# mcu.net
KiCad netlist of a schematic drawn in Altium Designer
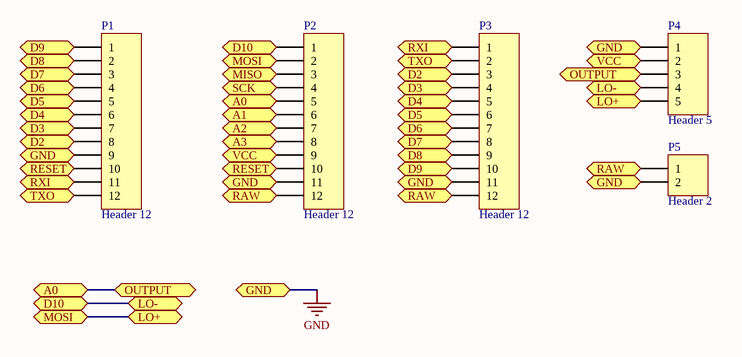
[diagram p0: mcu.SchDoc]

(export (version "E")
  (design (tool "Eeschema 10.0.6"))
  (components
    (comp (ref "P1")
      (value "Header 12")
      (footprint "HDR1X12")
      (description "Header, 12-Pin")
      (fields (field (name "PUBLISHER") "Altium Limited"))
      (libsource (lib "Miscellaneous Connectors") (part "Header 12"))
    )
    (comp (ref "P2")
      (value "Header 12")
      (footprint "HDR1X12")
      (description "Header, 12-Pin")
      (fields (field (name "PUBLISHER") "Altium Limited"))
      (libsource (lib "Miscellaneous Connectors") (part "Header 12"))
    )
    (comp (ref "P3")
      (value "Header 12")
      (footprint "HDR1X12")
      (description "Header, 12-Pin")
      (fields (field (name "PUBLISHER") "Altium Limited"))
      (libsource (lib "Miscellaneous Connectors") (part "Header 12"))
    )
    (comp (ref "P4")
      (value "Header 5")
      (footprint "HDR1X5")
      (description "Header, 5-Pin")
      (fields (field (name "PUBLISHER") "Altium Limited"))
      (libsource (lib "Miscellaneous Connectors") (part "Header 5"))
    )
    (comp (ref "P5")
      (value "Header 2")
      (footprint "HDR1X2")
      (description "Header, 2-Pin")
      (fields (field (name "PUBLISHER") "Altium Limited"))
      (libsource (lib "Miscellaneous Connectors") (part "Header 2"))
    )
  )
  (nets
    (net (code "1") (name "/A0") (class "Default")
      (node (ref "P2") (pin "5") (pinfunction "5_5") (pintype "passive"))
      (node (ref "P4") (pin "3") (pinfunction "3_3") (pintype "passive"))
    )
    (net (code "2") (name "/A1") (class "Default")
      (node (ref "P2") (pin "6") (pinfunction "6_6") (pintype "passive"))
    )
    (net (code "3") (name "/A2") (class "Default")
      (node (ref "P2") (pin "7") (pinfunction "7_7") (pintype "passive"))
    )
    (net (code "4") (name "/A3") (class "Default")
      (node (ref "P2") (pin "8") (pinfunction "8_8") (pintype "passive"))
    )
    (net (code "5") (name "/D2") (class "Default")
      (node (ref "P1") (pin "8") (pinfunction "8_8") (pintype "passive"))
      (node (ref "P3") (pin "3") (pinfunction "3_3") (pintype "passive"))
    )
    (net (code "6") (name "/D3") (class "Default")
      (node (ref "P1") (pin "7") (pinfunction "7_7") (pintype "passive"))
      (node (ref "P3") (pin "4") (pinfunction "4_4") (pintype "passive"))
    )
    (net (code "7") (name "/D4") (class "Default")
      (node (ref "P1") (pin "6") (pinfunction "6_6") (pintype "passive"))
      (node (ref "P3") (pin "5") (pinfunction "5_5") (pintype "passive"))
    )
    (net (code "8") (name "/D5") (class "Default")
      (node (ref "P1") (pin "5") (pinfunction "5_5") (pintype "passive"))
      (node (ref "P3") (pin "6") (pinfunction "6_6") (pintype "passive"))
    )
    (net (code "9") (name "/D6") (class "Default")
      (node (ref "P1") (pin "4") (pinfunction "4_4") (pintype "passive"))
      (node (ref "P3") (pin "7") (pinfunction "7_7") (pintype "passive"))
    )
    (net (code "10") (name "/D7") (class "Default")
      (node (ref "P1") (pin "3") (pinfunction "3_3") (pintype "passive"))
      (node (ref "P3") (pin "8") (pinfunction "8_8") (pintype "passive"))
    )
    (net (code "11") (name "/D8") (class "Default")
      (node (ref "P1") (pin "2") (pinfunction "2_2") (pintype "passive"))
      (node (ref "P3") (pin "9") (pinfunction "9_9") (pintype "passive"))
    )
    (net (code "12") (name "/D9") (class "Default")
      (node (ref "P1") (pin "1") (pinfunction "1_1") (pintype "passive"))
      (node (ref "P3") (pin "10") (pinfunction "10_10") (pintype "passive"))
    )
    (net (code "13") (name "/D10") (class "Default")
      (node (ref "P2") (pin "1") (pinfunction "1_1") (pintype "passive"))
      (node (ref "P4") (pin "4") (pinfunction "4_4") (pintype "passive"))
    )
    (net (code "14") (name "/LO+") (class "Default")
      (node (ref "P2") (pin "2") (pinfunction "2_2") (pintype "passive"))
      (node (ref "P4") (pin "5") (pinfunction "5_5") (pintype "passive"))
    )
    (net (code "15") (name "/MISO") (class "Default")
      (node (ref "P2") (pin "3") (pinfunction "3_3") (pintype "passive"))
    )
    (net (code "16") (name "/RAW") (class "Default")
      (node (ref "P2") (pin "12") (pinfunction "12_12") (pintype "passive"))
      (node (ref "P3") (pin "12") (pinfunction "12_12") (pintype "passive"))
      (node (ref "P5") (pin "1") (pinfunction "1_1") (pintype "passive"))
    )
    (net (code "17") (name "/RESET") (class "Default")
      (node (ref "P1") (pin "10") (pinfunction "10_10") (pintype "passive"))
      (node (ref "P2") (pin "10") (pinfunction "10_10") (pintype "passive"))
    )
    (net (code "18") (name "/RXI") (class "Default")
      (node (ref "P1") (pin "11") (pinfunction "11_11") (pintype "passive"))
      (node (ref "P3") (pin "1") (pinfunction "1_1") (pintype "passive"))
    )
    (net (code "19") (name "/SCK") (class "Default")
      (node (ref "P2") (pin "4") (pinfunction "4_4") (pintype "passive"))
    )
    (net (code "20") (name "/TXO") (class "Default")
      (node (ref "P1") (pin "12") (pinfunction "12_12") (pintype "passive"))
      (node (ref "P3") (pin "2") (pinfunction "2_2") (pintype "passive"))
    )
    (net (code "21") (name "/VCC") (class "Default")
      (node (ref "P2") (pin "9") (pinfunction "9_9") (pintype "passive"))
      (node (ref "P4") (pin "2") (pinfunction "2_2") (pintype "passive"))
    )
    (net (code "22") (name "GND") (class "Default")
      (node (ref "P1") (pin "9") (pinfunction "9_9") (pintype "passive"))
      (node (ref "P2") (pin "11") (pinfunction "11_11") (pintype "passive"))
      (node (ref "P3") (pin "11") (pinfunction "11_11") (pintype "passive"))
      (node (ref "P4") (pin "1") (pinfunction "1_1") (pintype "passive"))
      (node (ref "P5") (pin "2") (pinfunction "2_2") (pintype "passive"))
    )
  )
)
